# SensorBoard.net
KiCad netlist of a schematic drawn in Altium Designer
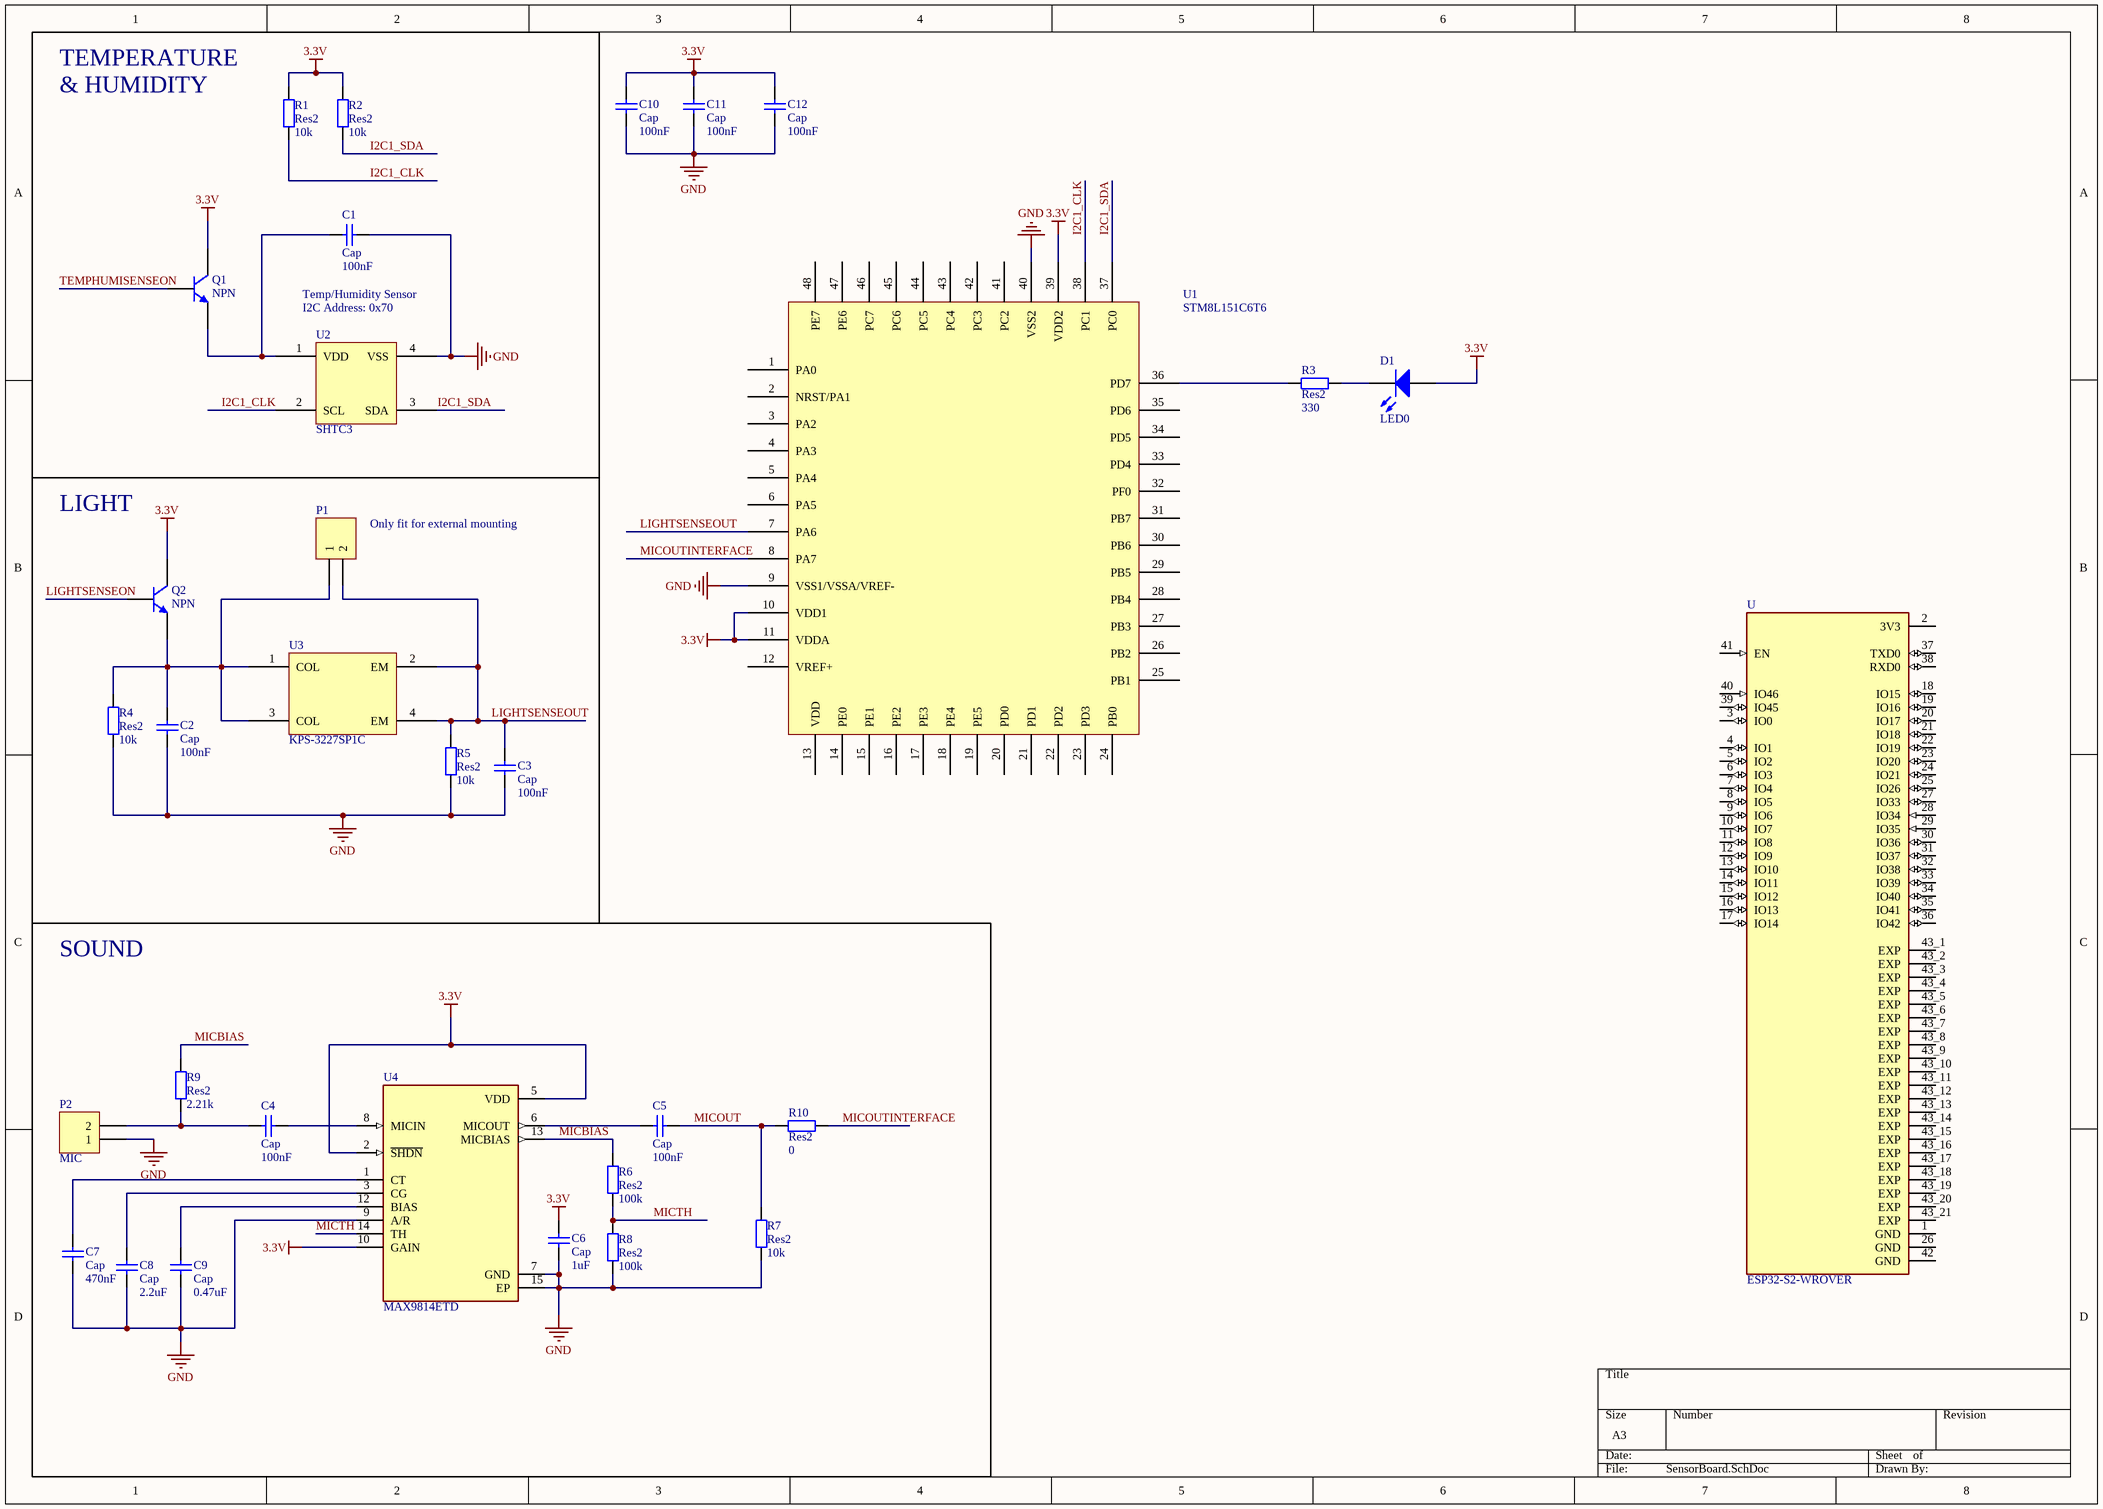
[diagram p0: SensorBoard.SchDoc]

(export (version "E")
  (design (tool "Eeschema 10.0.6"))
  (components
    (comp (ref "C1")
      (value "Cap")
      (footprint "RAD-0.3")
      (description "Capacitor")
      (fields (field (name "ALTIUM_VALUE") "100nF") (field (name "PUBLISHER") "Altium Limited"))
      (libsource (lib "Miscellaneous Devices") (part "Cap"))
    )
    (comp (ref "C2")
      (value "Cap")
      (footprint "RAD-0.3")
      (description "Capacitor")
      (fields (field (name "ALTIUM_VALUE") "100nF") (field (name "PUBLISHER") "Altium Limited"))
      (libsource (lib "Miscellaneous Devices") (part "Cap"))
    )
    (comp (ref "C3")
      (value "Cap")
      (footprint "RAD-0.3")
      (description "Capacitor")
      (fields (field (name "ALTIUM_VALUE") "100nF") (field (name "PUBLISHER") "Altium Limited"))
      (libsource (lib "Miscellaneous Devices") (part "Cap"))
    )
    (comp (ref "C4")
      (value "Cap")
      (footprint "RAD-0.3")
      (description "Capacitor")
      (fields (field (name "ALTIUM_VALUE") "100nF") (field (name "PUBLISHER") "Altium Limited"))
      (libsource (lib "Miscellaneous Devices") (part "Cap"))
    )
    (comp (ref "C5")
      (value "Cap")
      (footprint "RAD-0.3")
      (description "Capacitor")
      (fields (field (name "ALTIUM_VALUE") "100nF") (field (name "PUBLISHER") "Altium Limited"))
      (libsource (lib "Miscellaneous Devices") (part "Cap"))
    )
    (comp (ref "C6")
      (value "Cap")
      (footprint "RAD-0.3")
      (description "Capacitor")
      (fields (field (name "ALTIUM_VALUE") "1uF") (field (name "PUBLISHER") "Altium Limited"))
      (libsource (lib "Miscellaneous Devices") (part "Cap"))
    )
    (comp (ref "C7")
      (value "Cap")
      (footprint "RAD-0.3")
      (description "Capacitor")
      (fields (field (name "ALTIUM_VALUE") "470nF") (field (name "PUBLISHER") "Altium Limited"))
      (libsource (lib "Miscellaneous Devices") (part "Cap"))
    )
    (comp (ref "C8")
      (value "Cap")
      (footprint "RAD-0.3")
      (description "Capacitor")
      (fields (field (name "ALTIUM_VALUE") "2.2uF") (field (name "PUBLISHER") "Altium Limited"))
      (libsource (lib "Miscellaneous Devices") (part "Cap"))
    )
    (comp (ref "C9")
      (value "Cap")
      (footprint "RAD-0.3")
      (description "Capacitor")
      (fields (field (name "ALTIUM_VALUE") "0.47uF") (field (name "PUBLISHER") "Altium Limited"))
      (libsource (lib "Miscellaneous Devices") (part "Cap"))
    )
    (comp (ref "C10")
      (value "Cap")
      (footprint "RAD-0.3")
      (description "Capacitor")
      (fields (field (name "ALTIUM_VALUE") "100nF") (field (name "PUBLISHER") "Altium Limited"))
      (libsource (lib "Miscellaneous Devices") (part "Cap"))
    )
    (comp (ref "C11")
      (value "Cap")
      (footprint "RAD-0.3")
      (description "Capacitor")
      (fields (field (name "ALTIUM_VALUE") "100nF") (field (name "PUBLISHER") "Altium Limited"))
      (libsource (lib "Miscellaneous Devices") (part "Cap"))
    )
    (comp (ref "C12")
      (value "Cap")
      (footprint "RAD-0.3")
      (description "Capacitor")
      (fields (field (name "ALTIUM_VALUE") "100nF") (field (name "PUBLISHER") "Altium Limited"))
      (libsource (lib "Miscellaneous Devices") (part "Cap"))
    )
    (comp (ref "D1")
      (value "LED0")
      (footprint "LED-0")
      (description "Typical INFRARED GaAs LED")
      (fields (field (name "PUBLISHER") "Altium Limited"))
      (libsource (lib "Miscellaneous Devices") (part "LED0"))
    )
    (comp (ref "P1")
      (value "Only fit for external mounting")
      (footprint "HDR1X2")
      (description "Header, 2-Pin")
      (fields (field (name "PUBLISHER") "Altium Limited"))
      (libsource (lib "") (part "Header 2_1"))
    )
    (comp (ref "P2")
      (value "MIC")
      (footprint "HDR1X2")
      (description "Header, 2-Pin")
      (fields (field (name "PUBLISHER") "Altium Limited"))
      (libsource (lib "Miscellaneous Connectors") (part "Header 2"))
    )
    (comp (ref "Q1")
      (value "NPN")
      (footprint "TO-226-AA")
      (description "NPN Bipolar Transistor")
      (fields (field (name "PUBLISHER") "Altium Limited"))
      (libsource (lib "Miscellaneous Devices") (part "NPN"))
    )
    (comp (ref "Q2")
      (value "NPN")
      (footprint "TO-226-AA")
      (description "NPN Bipolar Transistor")
      (fields (field (name "PUBLISHER") "Altium Limited"))
      (libsource (lib "Miscellaneous Devices") (part "NPN"))
    )
    (comp (ref "R1")
      (value "Res2")
      (footprint "AXIAL-0.4")
      (description "Resistor")
      (fields (field (name "ALTIUM_VALUE") "10k") (field (name "PUBLISHER") "Altium Limited"))
      (libsource (lib "Miscellaneous Devices") (part "Res2"))
    )
    (comp (ref "R2")
      (value "Res2")
      (footprint "AXIAL-0.4")
      (description "Resistor")
      (fields (field (name "ALTIUM_VALUE") "10k") (field (name "PUBLISHER") "Altium Limited"))
      (libsource (lib "Miscellaneous Devices") (part "Res2"))
    )
    (comp (ref "R3")
      (value "Res2")
      (footprint "AXIAL-0.4")
      (description "Resistor")
      (fields (field (name "ALTIUM_VALUE") "330") (field (name "PUBLISHER") "Altium Limited"))
      (libsource (lib "") (part "Res2_1"))
    )
    (comp (ref "R4")
      (value "Res2")
      (footprint "AXIAL-0.4")
      (description "Resistor")
      (fields (field (name "ALTIUM_VALUE") "10k") (field (name "PUBLISHER") "Altium Limited"))
      (libsource (lib "Miscellaneous Devices") (part "Res2"))
    )
    (comp (ref "R5")
      (value "Res2")
      (footprint "AXIAL-0.4")
      (description "Resistor")
      (fields (field (name "ALTIUM_VALUE") "10k") (field (name "PUBLISHER") "Altium Limited"))
      (libsource (lib "Miscellaneous Devices") (part "Res2"))
    )
    (comp (ref "R6")
      (value "Res2")
      (footprint "AXIAL-0.4")
      (description "Resistor")
      (fields (field (name "ALTIUM_VALUE") "100k") (field (name "PUBLISHER") "Altium Limited"))
      (libsource (lib "Miscellaneous Devices") (part "Res2"))
    )
    (comp (ref "R7")
      (value "Res2")
      (footprint "AXIAL-0.4")
      (description "Resistor")
      (fields (field (name "ALTIUM_VALUE") "10k") (field (name "PUBLISHER") "Altium Limited"))
      (libsource (lib "Miscellaneous Devices") (part "Res2"))
    )
    (comp (ref "R8")
      (value "Res2")
      (footprint "AXIAL-0.4")
      (description "Resistor")
      (fields (field (name "ALTIUM_VALUE") "100k") (field (name "PUBLISHER") "Altium Limited"))
      (libsource (lib "Miscellaneous Devices") (part "Res2"))
    )
    (comp (ref "R9")
      (value "Res2")
      (footprint "AXIAL-0.4")
      (description "Resistor")
      (fields (field (name "ALTIUM_VALUE") "2.21k") (field (name "PUBLISHER") "Altium Limited"))
      (libsource (lib "Miscellaneous Devices") (part "Res2"))
    )
    (comp (ref "R10")
      (value "Res2")
      (footprint "AXIAL-0.4")
      (description "Resistor")
      (fields (field (name "ALTIUM_VALUE") "0") (field (name "PUBLISHER") "Altium Limited"))
      (libsource (lib "") (part "Res2_2"))
    )
    (comp (ref "U")
      (value "ESP32-S2-WROVER")
      (footprint "MODULE_ESP32-S2-WROVER")
      (description "WiFi 802.11b/g/n Transceiver Module 2.4GHz Antenna Not Included Surface Mount")
      (fields (field (name "MF") "Espressif Systems"))
      (libsource (lib "ESP32-S2-WROVER") (part "ESP32-S2-WROVER"))
    )
    (comp (ref "U1") (value "STM8L151C6T6") (libsource (lib "KurtSchemLib") (part "STM8L151C6T6")))
    (comp (ref "U2")
      (value "SHTC3")
      (fields (field (name "MANUFACTURER") "Sensirion"))
      (libsource (lib "KurtSchemLib") (part "SHTC3"))
    )
    (comp (ref "U3") (value "KPS-3227SP1C") (libsource (lib "KurtSchemLib") (part "KPS-3227SP1C")))
    (comp (ref "U4")
      (value "MAX9814ETD")
      (footprint "KurtLib:MAX9814ETD")
      (libsource (lib "KurtSchemLib") (part "MAX9814ETD"))
    )
  )
  (nets
    (net (code "1") (name "/I2C1_CLK") (class "Default")
      (node (ref "R1") (pin "1") (pinfunction "1_1") (pintype "passive"))
      (node (ref "U1") (pin "38") (pinfunction "PC1_38") (pintype "passive"))
      (node (ref "U2") (pin "2") (pinfunction "SCL_2") (pintype "passive"))
    )
    (net (code "2") (name "/I2C1_SDA") (class "Default")
      (node (ref "R2") (pin "1") (pinfunction "1_1") (pintype "passive"))
      (node (ref "U1") (pin "37") (pinfunction "PC0_37") (pintype "passive"))
      (node (ref "U2") (pin "3") (pinfunction "SDA_3") (pintype "passive"))
    )
    (net (code "3") (name "/LIGHTSENSEON") (class "Default")
      (node (ref "Q2") (pin "2") (pinfunction "B_2") (pintype "passive"))
    )
    (net (code "4") (name "/LIGHTSENSEOUT") (class "Default")
      (node (ref "C3") (pin "2") (pinfunction "2_2") (pintype "passive"))
      (node (ref "P1") (pin "2") (pinfunction "2_2") (pintype "passive"))
      (node (ref "R5") (pin "2") (pinfunction "2_2") (pintype "passive"))
      (node (ref "U1") (pin "7") (pinfunction "PA6_7") (pintype "passive"))
      (node (ref "U3") (pin "2") (pinfunction "EM_2") (pintype "passive"))
      (node (ref "U3") (pin "4") (pinfunction "EM_4") (pintype "passive"))
    )
    (net (code "5") (name "/MICBIAS") (class "Default")
      (node (ref "R6") (pin "2") (pinfunction "2_2") (pintype "passive"))
      (node (ref "R9") (pin "2") (pinfunction "2_2") (pintype "passive"))
      (node (ref "U4") (pin "13") (pinfunction "MICBIAS_13") (pintype "output"))
    )
    (net (code "6") (name "/MICOUT") (class "Default")
      (node (ref "C5") (pin "2") (pinfunction "2_2") (pintype "passive"))
      (node (ref "R10") (pin "2") (pinfunction "2_2") (pintype "passive"))
      (node (ref "R7") (pin "2") (pinfunction "2_2") (pintype "passive"))
    )
    (net (code "7") (name "/MICOUTINTERFACE") (class "Default")
      (node (ref "R10") (pin "1") (pinfunction "1_1") (pintype "passive"))
      (node (ref "U1") (pin "8") (pinfunction "PA7_8") (pintype "passive"))
    )
    (net (code "8") (name "/MICTH") (class "Default")
      (node (ref "R6") (pin "1") (pinfunction "1_1") (pintype "passive"))
      (node (ref "R8") (pin "2") (pinfunction "2_2") (pintype "passive"))
      (node (ref "U4") (pin "14") (pinfunction "TH_14") (pintype "passive"))
    )
    (net (code "9") (name "/TEMPHUMISENSEON") (class "Default")
      (node (ref "Q1") (pin "2") (pinfunction "B_2") (pintype "passive"))
    )
    (net (code "10") (name "3.3V") (class "Default")
      (node (ref "C10") (pin "2") (pinfunction "2_2") (pintype "passive"))
      (node (ref "C11") (pin "2") (pinfunction "2_2") (pintype "passive"))
      (node (ref "C12") (pin "2") (pinfunction "2_2") (pintype "passive"))
      (node (ref "C6") (pin "1") (pinfunction "1_1") (pintype "passive"))
      (node (ref "D1") (pin "1") (pinfunction "A_1") (pintype "passive"))
      (node (ref "Q1") (pin "1") (pinfunction "C_1") (pintype "passive"))
      (node (ref "Q2") (pin "1") (pinfunction "C_1") (pintype "passive"))
      (node (ref "R1") (pin "2") (pinfunction "2_2") (pintype "passive"))
      (node (ref "R2") (pin "2") (pinfunction "2_2") (pintype "passive"))
      (node (ref "U1") (pin "10") (pinfunction "VDD1_10") (pintype "passive"))
      (node (ref "U1") (pin "11") (pinfunction "VDDA_11") (pintype "passive"))
      (node (ref "U1") (pin "39") (pinfunction "VDD2_39") (pintype "passive"))
      (node (ref "U4") (pin "10") (pinfunction "GAIN_10") (pintype "passive"))
      (node (ref "U4") (pin "2") (pinfunction "~{SHDN}_2") (pintype "input"))
      (node (ref "U4") (pin "5") (pinfunction "VDD_5") (pintype "power_in"))
    )
    (net (code "11") (name "GND") (class "Default")
      (node (ref "C1") (pin "2") (pinfunction "2_2") (pintype "passive"))
      (node (ref "C10") (pin "1") (pinfunction "1_1") (pintype "passive"))
      (node (ref "C11") (pin "1") (pinfunction "1_1") (pintype "passive"))
      (node (ref "C12") (pin "1") (pinfunction "1_1") (pintype "passive"))
      (node (ref "C2") (pin "1") (pinfunction "1_1") (pintype "passive"))
      (node (ref "C3") (pin "1") (pinfunction "1_1") (pintype "passive"))
      (node (ref "C6") (pin "2") (pinfunction "2_2") (pintype "passive"))
      (node (ref "C7") (pin "2") (pinfunction "2_2") (pintype "passive"))
      (node (ref "C8") (pin "2") (pinfunction "2_2") (pintype "passive"))
      (node (ref "C9") (pin "2") (pinfunction "2_2") (pintype "passive"))
      (node (ref "P2") (pin "1") (pinfunction "1_1") (pintype "passive"))
      (node (ref "R4") (pin "1") (pinfunction "1_1") (pintype "passive"))
      (node (ref "R5") (pin "1") (pinfunction "1_1") (pintype "passive"))
      (node (ref "R7") (pin "1") (pinfunction "1_1") (pintype "passive"))
      (node (ref "R8") (pin "1") (pinfunction "1_1") (pintype "passive"))
      (node (ref "U1") (pin "40") (pinfunction "VSS2_40") (pintype "passive"))
      (node (ref "U1") (pin "9") (pinfunction "VSS1/VSSA/VREF-_9") (pintype "passive"))
      (node (ref "U2") (pin "4") (pinfunction "VSS_4") (pintype "passive"))
      (node (ref "U4") (pin "15") (pinfunction "EP_15") (pintype "power_in"))
      (node (ref "U4") (pin "7") (pinfunction "GND_7") (pintype "power_in"))
      (node (ref "U4") (pin "9") (pinfunction "A/R_9") (pintype "passive"))
    )
    (net (code "12") (name "Net-(C4-Pad1)") (class "Default")
      (node (ref "C4") (pin "1") (pinfunction "1_1") (pintype "passive"))
      (node (ref "P2") (pin "2") (pinfunction "2_2") (pintype "passive"))
      (node (ref "R9") (pin "1") (pinfunction "1_1") (pintype "passive"))
    )
    (net (code "13") (name "Net-(D1-K)") (class "Default")
      (node (ref "D1") (pin "2") (pinfunction "K_2") (pintype "passive"))
      (node (ref "R3") (pin "2") (pinfunction "2_2") (pintype "passive"))
    )
    (net (code "14") (name "Net-(Q1-E)") (class "Default")
      (node (ref "C1") (pin "1") (pinfunction "1_1") (pintype "passive"))
      (node (ref "Q1") (pin "3") (pinfunction "E_3") (pintype "passive"))
      (node (ref "U2") (pin "1") (pinfunction "VDD_1") (pintype "passive"))
    )
    (net (code "15") (name "Net-(Q2-E)") (class "Default")
      (node (ref "C2") (pin "2") (pinfunction "2_2") (pintype "passive"))
      (node (ref "P1") (pin "1") (pinfunction "1_1") (pintype "passive"))
      (node (ref "Q2") (pin "3") (pinfunction "E_3") (pintype "passive"))
      (node (ref "R4") (pin "2") (pinfunction "2_2") (pintype "passive"))
      (node (ref "U3") (pin "1") (pinfunction "COL_1") (pintype "passive"))
      (node (ref "U3") (pin "3") (pinfunction "COL_3") (pintype "passive"))
    )
    (net (code "16") (name "Net-(U1-PD7)") (class "Default")
      (node (ref "R3") (pin "1") (pinfunction "1_1") (pintype "passive"))
      (node (ref "U1") (pin "36") (pinfunction "PD7_36") (pintype "passive"))
    )
    (net (code "17") (name "Net-(U4-BIAS)") (class "Default")
      (node (ref "C9") (pin "1") (pinfunction "1_1") (pintype "passive"))
      (node (ref "U4") (pin "12") (pinfunction "BIAS_12") (pintype "passive"))
    )
    (net (code "18") (name "Net-(U4-CG)") (class "Default")
      (node (ref "C8") (pin "1") (pinfunction "1_1") (pintype "passive"))
      (node (ref "U4") (pin "3") (pinfunction "CG_3") (pintype "passive"))
    )
    (net (code "19") (name "Net-(U4-CT)") (class "Default")
      (node (ref "C7") (pin "1") (pinfunction "1_1") (pintype "passive"))
      (node (ref "U4") (pin "1") (pinfunction "CT_1") (pintype "passive"))
    )
    (net (code "20") (name "Net-(U4-MICIN)") (class "Default")
      (node (ref "C4") (pin "2") (pinfunction "2_2") (pintype "passive"))
      (node (ref "U4") (pin "8") (pinfunction "MICIN_8") (pintype "input"))
    )
    (net (code "21") (name "Net-(U4-MICOUT)") (class "Default")
      (node (ref "C5") (pin "1") (pinfunction "1_1") (pintype "passive"))
      (node (ref "U4") (pin "6") (pinfunction "MICOUT_6") (pintype "output"))
    )
    (net (code "22") (name "unconnected-(U-3V3-Pad2)") (class "Default")
      (node (ref "U") (pin "2") (pinfunction "3V3_2") (pintype "power_in"))
    )
    (net (code "23") (name "unconnected-(U-EN-Pad41)") (class "Default")
      (node (ref "U") (pin "41") (pinfunction "EN_41") (pintype "input"))
    )
    (net (code "24") (name "unconnected-(U-EXP-Pad43_1)") (class "Default")
      (node (ref "U") (pin "43_1") (pinfunction "EXP_43_1") (pintype "power_in"))
    )
    (net (code "25") (name "unconnected-(U-EXP-Pad43_2)") (class "Default")
      (node (ref "U") (pin "43_2") (pinfunction "EXP_43_2") (pintype "power_in"))
    )
    (net (code "26") (name "unconnected-(U-EXP-Pad43_3)") (class "Default")
      (node (ref "U") (pin "43_3") (pinfunction "EXP_43_3") (pintype "power_in"))
    )
    (net (code "27") (name "unconnected-(U-EXP-Pad43_4)") (class "Default")
      (node (ref "U") (pin "43_4") (pinfunction "EXP_43_4") (pintype "power_in"))
    )
    (net (code "28") (name "unconnected-(U-EXP-Pad43_5)") (class "Default")
      (node (ref "U") (pin "43_5") (pinfunction "EXP_43_5") (pintype "power_in"))
    )
    (net (code "29") (name "unconnected-(U-EXP-Pad43_6)") (class "Default")
      (node (ref "U") (pin "43_6") (pinfunction "EXP_43_6") (pintype "power_in"))
    )
    (net (code "30") (name "unconnected-(U-EXP-Pad43_7)") (class "Default")
      (node (ref "U") (pin "43_7") (pinfunction "EXP_43_7") (pintype "power_in"))
    )
    (net (code "31") (name "unconnected-(U-EXP-Pad43_8)") (class "Default")
      (node (ref "U") (pin "43_8") (pinfunction "EXP_43_8") (pintype "power_in"))
    )
    (net (code "32") (name "unconnected-(U-EXP-Pad43_9)") (class "Default")
      (node (ref "U") (pin "43_9") (pinfunction "EXP_43_9") (pintype "power_in"))
    )
    (net (code "33") (name "unconnected-(U-EXP-Pad43_10)") (class "Default")
      (node (ref "U") (pin "43_10") (pinfunction "EXP_43_10") (pintype "power_in"))
    )
    (net (code "34") (name "unconnected-(U-EXP-Pad43_11)") (class "Default")
      (node (ref "U") (pin "43_11") (pinfunction "EXP_43_11") (pintype "power_in"))
    )
    (net (code "35") (name "unconnected-(U-EXP-Pad43_12)") (class "Default")
      (node (ref "U") (pin "43_12") (pinfunction "EXP_43_12") (pintype "power_in"))
    )
    (net (code "36") (name "unconnected-(U-EXP-Pad43_13)") (class "Default")
      (node (ref "U") (pin "43_13") (pinfunction "EXP_43_13") (pintype "power_in"))
    )
    (net (code "37") (name "unconnected-(U-EXP-Pad43_14)") (class "Default")
      (node (ref "U") (pin "43_14") (pinfunction "EXP_43_14") (pintype "power_in"))
    )
    (net (code "38") (name "unconnected-(U-EXP-Pad43_15)") (class "Default")
      (node (ref "U") (pin "43_15") (pinfunction "EXP_43_15") (pintype "power_in"))
    )
    (net (code "39") (name "unconnected-(U-EXP-Pad43_16)") (class "Default")
      (node (ref "U") (pin "43_16") (pinfunction "EXP_43_16") (pintype "power_in"))
    )
    (net (code "40") (name "unconnected-(U-EXP-Pad43_17)") (class "Default")
      (node (ref "U") (pin "43_17") (pinfunction "EXP_43_17") (pintype "power_in"))
    )
    (net (code "41") (name "unconnected-(U-EXP-Pad43_18)") (class "Default")
      (node (ref "U") (pin "43_18") (pinfunction "EXP_43_18") (pintype "power_in"))
    )
    (net (code "42") (name "unconnected-(U-EXP-Pad43_19)") (class "Default")
      (node (ref "U") (pin "43_19") (pinfunction "EXP_43_19") (pintype "power_in"))
    )
    (net (code "43") (name "unconnected-(U-EXP-Pad43_20)") (class "Default")
      (node (ref "U") (pin "43_20") (pinfunction "EXP_43_20") (pintype "power_in"))
    )
    (net (code "44") (name "unconnected-(U-EXP-Pad43_21)") (class "Default")
      (node (ref "U") (pin "43_21") (pinfunction "EXP_43_21") (pintype "power_in"))
    )
    (net (code "45") (name "unconnected-(U-GND-Pad1)") (class "Default")
      (node (ref "U") (pin "1") (pinfunction "GND_1") (pintype "power_in"))
    )
    (net (code "46") (name "unconnected-(U-GND-Pad26)") (class "Default")
      (node (ref "U") (pin "26") (pinfunction "GND_26") (pintype "power_in"))
    )
    (net (code "47") (name "unconnected-(U-GND-Pad42)") (class "Default")
      (node (ref "U") (pin "42") (pinfunction "GND_42") (pintype "power_in"))
    )
    (net (code "48") (name "unconnected-(U-IO0-Pad3)") (class "Default")
      (node (ref "U") (pin "3") (pinfunction "IO0_3") (pintype "bidirectional"))
    )
    (net (code "49") (name "unconnected-(U-IO1-Pad4)") (class "Default")
      (node (ref "U") (pin "4") (pinfunction "IO1_4") (pintype "bidirectional"))
    )
    (net (code "50") (name "unconnected-(U-IO2-Pad5)") (class "Default")
      (node (ref "U") (pin "5") (pinfunction "IO2_5") (pintype "bidirectional"))
    )
    (net (code "51") (name "unconnected-(U-IO3-Pad6)") (class "Default")
      (node (ref "U") (pin "6") (pinfunction "IO3_6") (pintype "bidirectional"))
    )
    (net (code "52") (name "unconnected-(U-IO4-Pad7)") (class "Default")
      (node (ref "U") (pin "7") (pinfunction "IO4_7") (pintype "bidirectional"))
    )
    (net (code "53") (name "unconnected-(U-IO5-Pad8)") (class "Default")
      (node (ref "U") (pin "8") (pinfunction "IO5_8") (pintype "bidirectional"))
    )
    (net (code "54") (name "unconnected-(U-IO6-Pad9)") (class "Default")
      (node (ref "U") (pin "9") (pinfunction "IO6_9") (pintype "bidirectional"))
    )
    (net (code "55") (name "unconnected-(U-IO7-Pad10)") (class "Default")
      (node (ref "U") (pin "10") (pinfunction "IO7_10") (pintype "bidirectional"))
    )
    (net (code "56") (name "unconnected-(U-IO8-Pad11)") (class "Default")
      (node (ref "U") (pin "11") (pinfunction "IO8_11") (pintype "bidirectional"))
    )
    (net (code "57") (name "unconnected-(U-IO9-Pad12)") (class "Default")
      (node (ref "U") (pin "12") (pinfunction "IO9_12") (pintype "bidirectional"))
    )
    (net (code "58") (name "unconnected-(U-IO10-Pad13)") (class "Default")
      (node (ref "U") (pin "13") (pinfunction "IO10_13") (pintype "bidirectional"))
    )
    (net (code "59") (name "unconnected-(U-IO11-Pad14)") (class "Default")
      (node (ref "U") (pin "14") (pinfunction "IO11_14") (pintype "bidirectional"))
    )
    (net (code "60") (name "unconnected-(U-IO12-Pad15)") (class "Default")
      (node (ref "U") (pin "15") (pinfunction "IO12_15") (pintype "bidirectional"))
    )
    (net (code "61") (name "unconnected-(U-IO13-Pad16)") (class "Default")
      (node (ref "U") (pin "16") (pinfunction "IO13_16") (pintype "bidirectional"))
    )
    (net (code "62") (name "unconnected-(U-IO14-Pad17)") (class "Default")
      (node (ref "U") (pin "17") (pinfunction "IO14_17") (pintype "bidirectional"))
    )
    (net (code "63") (name "unconnected-(U-IO15-Pad18)") (class "Default")
      (node (ref "U") (pin "18") (pinfunction "IO15_18") (pintype "bidirectional"))
    )
    (net (code "64") (name "unconnected-(U-IO16-Pad19)") (class "Default")
      (node (ref "U") (pin "19") (pinfunction "IO16_19") (pintype "bidirectional"))
    )
    (net (code "65") (name "unconnected-(U-IO17-Pad20)") (class "Default")
      (node (ref "U") (pin "20") (pinfunction "IO17_20") (pintype "bidirectional"))
    )
    (net (code "66") (name "unconnected-(U-IO18-Pad21)") (class "Default")
      (node (ref "U") (pin "21") (pinfunction "IO18_21") (pintype "bidirectional"))
    )
    (net (code "67") (name "unconnected-(U-IO19-Pad22)") (class "Default")
      (node (ref "U") (pin "22") (pinfunction "IO19_22") (pintype "bidirectional"))
    )
    (net (code "68") (name "unconnected-(U-IO20-Pad23)") (class "Default")
      (node (ref "U") (pin "23") (pinfunction "IO20_23") (pintype "bidirectional"))
    )
    (net (code "69") (name "unconnected-(U-IO21-Pad24)") (class "Default")
      (node (ref "U") (pin "24") (pinfunction "IO21_24") (pintype "bidirectional"))
    )
    (net (code "70") (name "unconnected-(U-IO26-Pad25)") (class "Default")
      (node (ref "U") (pin "25") (pinfunction "IO26_25") (pintype "bidirectional"))
    )
    (net (code "71") (name "unconnected-(U-IO33-Pad27)") (class "Default")
      (node (ref "U") (pin "27") (pinfunction "IO33_27") (pintype "bidirectional"))
    )
    (net (code "72") (name "unconnected-(U-IO34-Pad28)") (class "Default")
      (node (ref "U") (pin "28") (pinfunction "IO34_28") (pintype "input"))
    )
    (net (code "73") (name "unconnected-(U-IO35-Pad29)") (class "Default")
      (node (ref "U") (pin "29") (pinfunction "IO35_29") (pintype "input"))
    )
    (net (code "74") (name "unconnected-(U-IO36-Pad30)") (class "Default")
      (node (ref "U") (pin "30") (pinfunction "IO36_30") (pintype "bidirectional"))
    )
    (net (code "75") (name "unconnected-(U-IO37-Pad31)") (class "Default")
      (node (ref "U") (pin "31") (pinfunction "IO37_31") (pintype "bidirectional"))
    )
    (net (code "76") (name "unconnected-(U-IO38-Pad32)") (class "Default")
      (node (ref "U") (pin "32") (pinfunction "IO38_32") (pintype "bidirectional"))
    )
    (net (code "77") (name "unconnected-(U-IO39-Pad33)") (class "Default")
      (node (ref "U") (pin "33") (pinfunction "IO39_33") (pintype "bidirectional"))
    )
    (net (code "78") (name "unconnected-(U-IO40-Pad34)") (class "Default")
      (node (ref "U") (pin "34") (pinfunction "IO40_34") (pintype "bidirectional"))
    )
    (net (code "79") (name "unconnected-(U-IO41-Pad35)") (class "Default")
      (node (ref "U") (pin "35") (pinfunction "IO41_35") (pintype "bidirectional"))
    )
    (net (code "80") (name "unconnected-(U-IO42-Pad36)") (class "Default")
      (node (ref "U") (pin "36") (pinfunction "IO42_36") (pintype "bidirectional"))
    )
    (net (code "81") (name "unconnected-(U-IO45-Pad39)") (class "Default")
      (node (ref "U") (pin "39") (pinfunction "IO45_39") (pintype "bidirectional"))
    )
    (net (code "82") (name "unconnected-(U-IO46-Pad40)") (class "Default")
      (node (ref "U") (pin "40") (pinfunction "IO46_40") (pintype "input"))
    )
    (net (code "83") (name "unconnected-(U-RXD0-Pad38)") (class "Default")
      (node (ref "U") (pin "38") (pinfunction "RXD0_38") (pintype "bidirectional"))
    )
    (net (code "84") (name "unconnected-(U-TXD0-Pad37)") (class "Default")
      (node (ref "U") (pin "37") (pinfunction "TXD0_37") (pintype "bidirectional"))
    )
    (net (code "85") (name "unconnected-(U1-NRST{slash}PA1-Pad2)") (class "Default")
      (node (ref "U1") (pin "2") (pinfunction "NRST/PA1_2") (pintype "passive"))
    )
    (net (code "86") (name "unconnected-(U1-PA0-Pad1)") (class "Default")
      (node (ref "U1") (pin "1") (pinfunction "PA0_1") (pintype "passive"))
    )
    (net (code "87") (name "unconnected-(U1-PA2-Pad3)") (class "Default")
      (node (ref "U1") (pin "3") (pinfunction "PA2_3") (pintype "passive"))
    )
    (net (code "88") (name "unconnected-(U1-PA3-Pad4)") (class "Default")
      (node (ref "U1") (pin "4") (pinfunction "PA3_4") (pintype "passive"))
    )
    (net (code "89") (name "unconnected-(U1-PA4-Pad5)") (class "Default")
      (node (ref "U1") (pin "5") (pinfunction "PA4_5") (pintype "passive"))
    )
    (net (code "90") (name "unconnected-(U1-PA5-Pad6)") (class "Default")
      (node (ref "U1") (pin "6") (pinfunction "PA5_6") (pintype "passive"))
    )
    (net (code "91") (name "unconnected-(U1-PB0-Pad24)") (class "Default")
      (node (ref "U1") (pin "24") (pinfunction "PB0_24") (pintype "passive"))
    )
    (net (code "92") (name "unconnected-(U1-PB1-Pad25)") (class "Default")
      (node (ref "U1") (pin "25") (pinfunction "PB1_25") (pintype "passive"))
    )
    (net (code "93") (name "unconnected-(U1-PB2-Pad26)") (class "Default")
      (node (ref "U1") (pin "26") (pinfunction "PB2_26") (pintype "passive"))
    )
    (net (code "94") (name "unconnected-(U1-PB3-Pad27)") (class "Default")
      (node (ref "U1") (pin "27") (pinfunction "PB3_27") (pintype "passive"))
    )
    (net (code "95") (name "unconnected-(U1-PB4-Pad28)") (class "Default")
      (node (ref "U1") (pin "28") (pinfunction "PB4_28") (pintype "passive"))
    )
    (net (code "96") (name "unconnected-(U1-PB5-Pad29)") (class "Default")
      (node (ref "U1") (pin "29") (pinfunction "PB5_29") (pintype "passive"))
    )
    (net (code "97") (name "unconnected-(U1-PB6-Pad30)") (class "Default")
      (node (ref "U1") (pin "30") (pinfunction "PB6_30") (pintype "passive"))
    )
    (net (code "98") (name "unconnected-(U1-PB7-Pad31)") (class "Default")
      (node (ref "U1") (pin "31") (pinfunction "PB7_31") (pintype "passive"))
    )
    (net (code "99") (name "unconnected-(U1-PC2-Pad41)") (class "Default")
      (node (ref "U1") (pin "41") (pinfunction "PC2_41") (pintype "passive"))
    )
    (net (code "100") (name "unconnected-(U1-PC3-Pad42)") (class "Default")
      (node (ref "U1") (pin "42") (pinfunction "PC3_42") (pintype "passive"))
    )
    (net (code "101") (name "unconnected-(U1-PC4-Pad43)") (class "Default")
      (node (ref "U1") (pin "43") (pinfunction "PC4_43") (pintype "passive"))
    )
    (net (code "102") (name "unconnected-(U1-PC5-Pad44)") (class "Default")
      (node (ref "U1") (pin "44") (pinfunction "PC5_44") (pintype "passive"))
    )
    (net (code "103") (name "unconnected-(U1-PC6-Pad45)") (class "Default")
      (node (ref "U1") (pin "45") (pinfunction "PC6_45") (pintype "passive"))
    )
    (net (code "104") (name "unconnected-(U1-PC7-Pad46)") (class "Default")
      (node (ref "U1") (pin "46") (pinfunction "PC7_46") (pintype "passive"))
    )
    (net (code "105") (name "unconnected-(U1-PD0-Pad20)") (class "Default")
      (node (ref "U1") (pin "20") (pinfunction "PD0_20") (pintype "passive"))
    )
    (net (code "106") (name "unconnected-(U1-PD1-Pad21)") (class "Default")
      (node (ref "U1") (pin "21") (pinfunction "PD1_21") (pintype "passive"))
    )
    (net (code "107") (name "unconnected-(U1-PD2-Pad22)") (class "Default")
      (node (ref "U1") (pin "22") (pinfunction "PD2_22") (pintype "passive"))
    )
    (net (code "108") (name "unconnected-(U1-PD3-Pad23)") (class "Default")
      (node (ref "U1") (pin "23") (pinfunction "PD3_23") (pintype "passive"))
    )
    (net (code "109") (name "unconnected-(U1-PD4-Pad33)") (class "Default")
      (node (ref "U1") (pin "33") (pinfunction "PD4_33") (pintype "passive"))
    )
    (net (code "110") (name "unconnected-(U1-PD5-Pad34)") (class "Default")
      (node (ref "U1") (pin "34") (pinfunction "PD5_34") (pintype "passive"))
    )
    (net (code "111") (name "unconnected-(U1-PD6-Pad35)") (class "Default")
      (node (ref "U1") (pin "35") (pinfunction "PD6_35") (pintype "passive"))
    )
    (net (code "112") (name "unconnected-(U1-PE0-Pad14)") (class "Default")
      (node (ref "U1") (pin "14") (pinfunction "PE0_14") (pintype "passive"))
    )
    (net (code "113") (name "unconnected-(U1-PE1-Pad15)") (class "Default")
      (node (ref "U1") (pin "15") (pinfunction "PE1_15") (pintype "passive"))
    )
    (net (code "114") (name "unconnected-(U1-PE2-Pad16)") (class "Default")
      (node (ref "U1") (pin "16") (pinfunction "PE2_16") (pintype "passive"))
    )
    (net (code "115") (name "unconnected-(U1-PE3-Pad17)") (class "Default")
      (node (ref "U1") (pin "17") (pinfunction "PE3_17") (pintype "passive"))
    )
    (net (code "116") (name "unconnected-(U1-PE4-Pad18)") (class "Default")
      (node (ref "U1") (pin "18") (pinfunction "PE4_18") (pintype "passive"))
    )
    (net (code "117") (name "unconnected-(U1-PE5-Pad19)") (class "Default")
      (node (ref "U1") (pin "19") (pinfunction "PE5_19") (pintype "passive"))
    )
    (net (code "118") (name "unconnected-(U1-PE6-Pad47)") (class "Default")
      (node (ref "U1") (pin "47") (pinfunction "PE6_47") (pintype "passive"))
    )
    (net (code "119") (name "unconnected-(U1-PE7-Pad48)") (class "Default")
      (node (ref "U1") (pin "48") (pinfunction "PE7_48") (pintype "passive"))
    )
    (net (code "120") (name "unconnected-(U1-PF0-Pad32)") (class "Default")
      (node (ref "U1") (pin "32") (pinfunction "PF0_32") (pintype "passive"))
    )
    (net (code "121") (name "unconnected-(U1-VDD-Pad13)") (class "Default")
      (node (ref "U1") (pin "13") (pinfunction "VDD_13") (pintype "passive"))
    )
    (net (code "122") (name "unconnected-(U1-VREF+-Pad12)") (class "Default")
      (node (ref "U1") (pin "12") (pinfunction "VREF+_12") (pintype "passive"))
    )
  )
)
